# uStar_v1.net
KiCad netlist of a schematic drawn in EAGLE
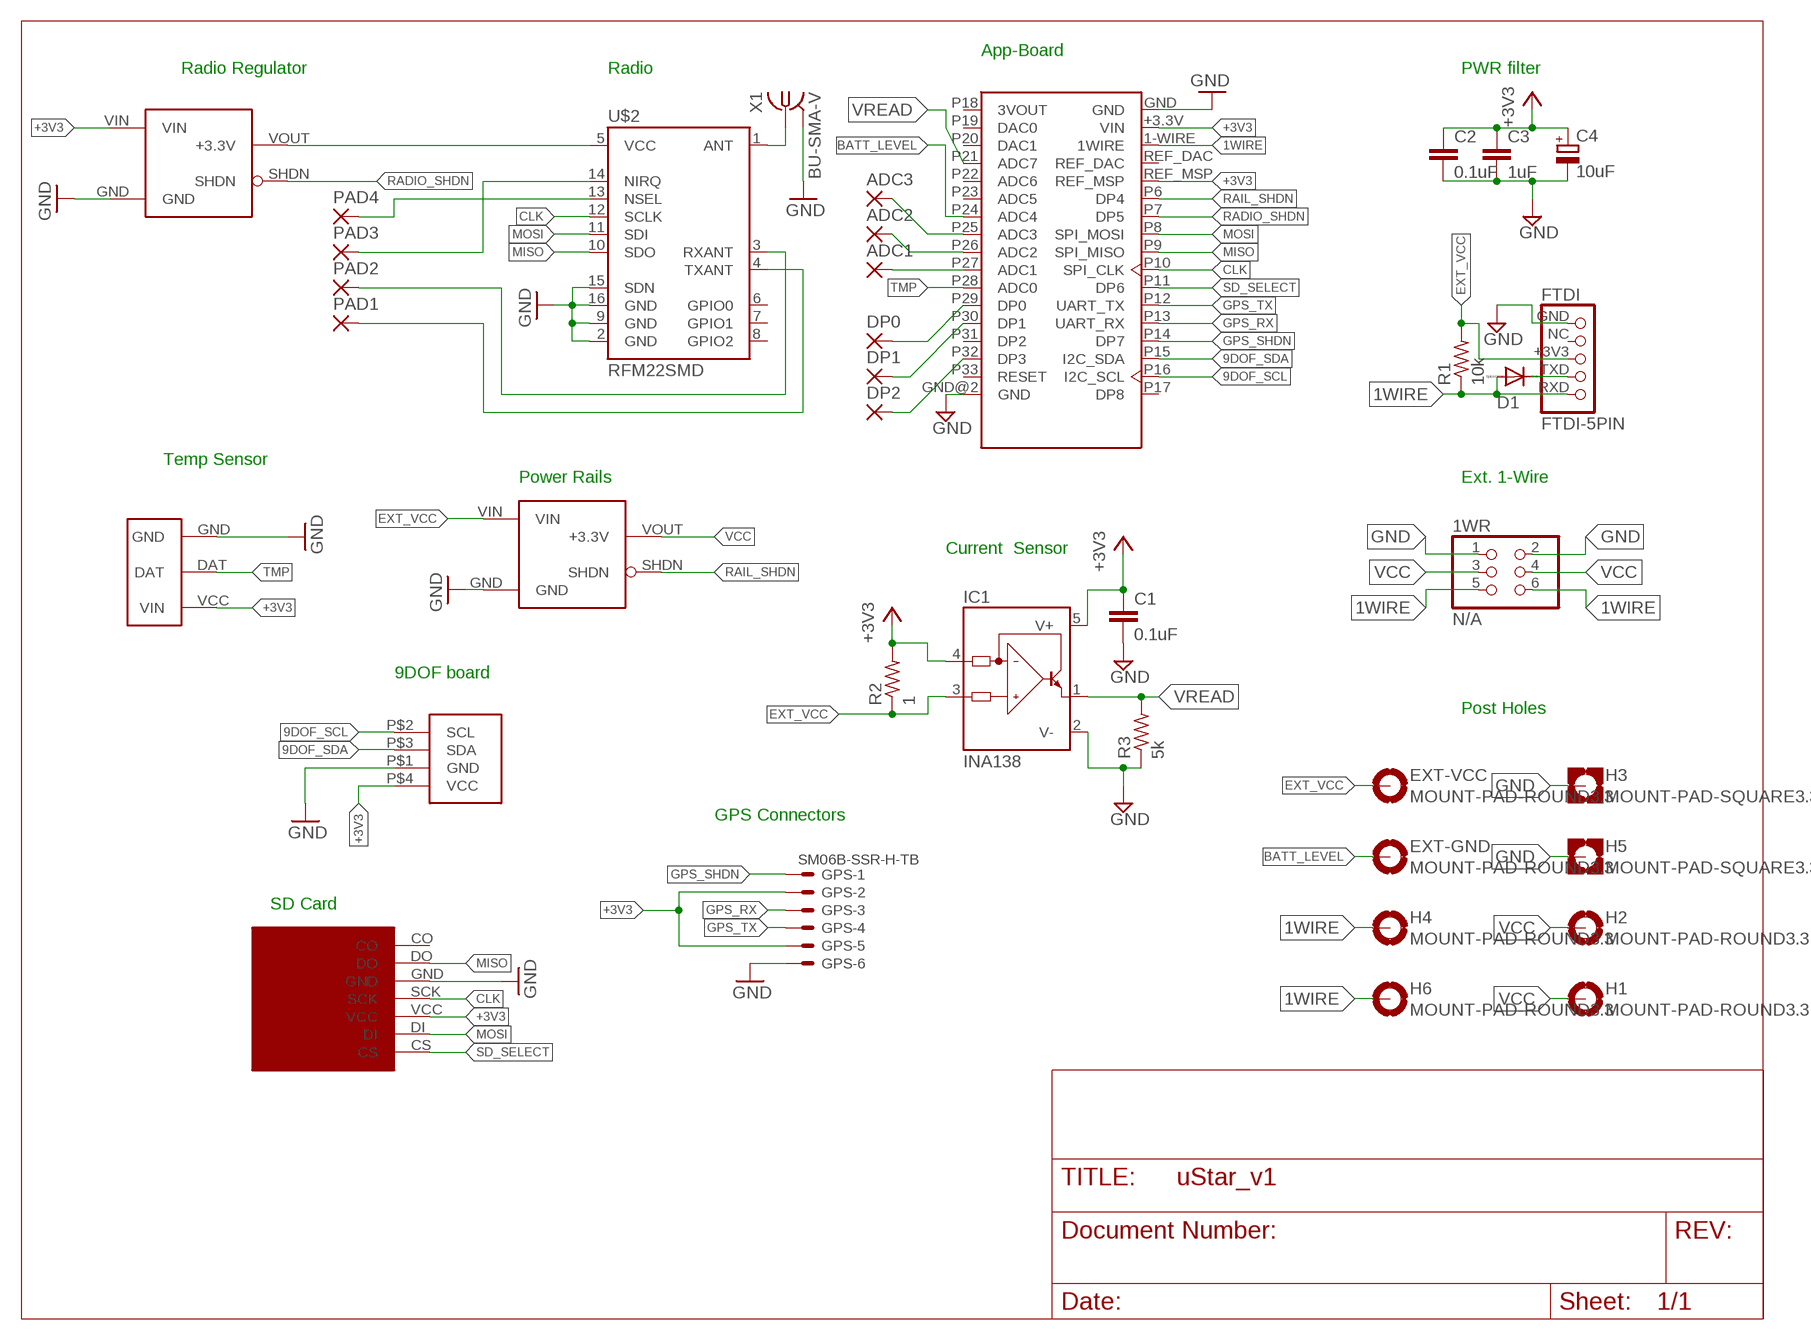
[diagram p0: schematic, sheet 1]

(export (version "E")
  (design (tool "Eeschema 10.0.6"))
  (components
    (comp (ref "1WR")
      (value "N/A")
      (footprint "eagle-import:2X03")
      (libsource (lib "eagle-import") (part "PINHD-2X3"))
    )
    (comp (ref "ADC1")
      (value "1,6/0,9")
      (footprint "eagle-import:1,6_0,9")
      (libsource (lib "eagle-import") (part "1,6/0,9"))
    )
    (comp (ref "ADC2")
      (value "1,6/0,9")
      (footprint "eagle-import:1,6_0,9")
      (libsource (lib "eagle-import") (part "1,6/0,9"))
    )
    (comp (ref "ADC3")
      (value "1,6/0,9")
      (footprint "eagle-import:1,6_0,9")
      (libsource (lib "eagle-import") (part "1,6/0,9"))
    )
    (comp (ref "C1")
      (value "0.1uF")
      (footprint "eagle-import:C0805")
      (libsource (lib "eagle-import") (part "C-EUC0805"))
    )
    (comp (ref "C2")
      (value "0.1uF")
      (footprint "eagle-import:C0603")
      (libsource (lib "eagle-import") (part "C-EUC0603"))
    )
    (comp (ref "C3")
      (value "1uF")
      (footprint "eagle-import:C0603")
      (libsource (lib "eagle-import") (part "C-EUC0603"))
    )
    (comp (ref "C4")
      (value "10uF")
      (footprint "eagle-import:SMC_B")
      (libsource (lib "eagle-import") (part "CPOL-EUSMCB"))
    )
    (comp (ref "D1")
      (value "1N4148DO35-7")
      (footprint "eagle-import:DO35-7")
      (libsource (lib "eagle-import") (part "1N4148DO35-7"))
    )
    (comp (ref "DP0")
      (value "1,6/0,9")
      (footprint "eagle-import:1,6_0,9")
      (libsource (lib "eagle-import") (part "1,6/0,9"))
    )
    (comp (ref "DP1")
      (value "1,6/0,9")
      (footprint "eagle-import:1,6_0,9")
      (libsource (lib "eagle-import") (part "1,6/0,9"))
    )
    (comp (ref "DP2")
      (value "1,6/0,9")
      (footprint "eagle-import:1,6_0,9")
      (libsource (lib "eagle-import") (part "1,6/0,9"))
    )
    (comp (ref "EXT-GND")
      (value "MOUNT-PAD-ROUND3.3")
      (footprint "eagle-import:3,3-PAD")
      (libsource (lib "eagle-import") (part "MOUNT-PAD-ROUND3.3"))
    )
    (comp (ref "EXT-VCC")
      (value "MOUNT-PAD-ROUND3.3")
      (footprint "eagle-import:3,3-PAD")
      (libsource (lib "eagle-import") (part "MOUNT-PAD-ROUND3.3"))
    )
    (comp (ref "FTDI")
      (value "FTDI-5PIN")
      (footprint "eagle-import:1_05X2MM")
      (libsource (lib "eagle-import") (part "FTDI-5PIN"))
    )
    (comp (ref "GPS")
      (value "SM06B-SSR-H-TB")
      (footprint "eagle-import:SM06B-SSR-H-TB")
      (libsource (lib "eagle-import") (part "SM06B-SSR-H-TB"))
    )
    (comp (ref "H1")
      (value "MOUNT-PAD-ROUND3.3")
      (footprint "eagle-import:3,3-PAD")
      (libsource (lib "eagle-import") (part "MOUNT-PAD-ROUND3.3"))
    )
    (comp (ref "H2")
      (value "MOUNT-PAD-ROUND3.3")
      (footprint "eagle-import:3,3-PAD")
      (libsource (lib "eagle-import") (part "MOUNT-PAD-ROUND3.3"))
    )
    (comp (ref "H3")
      (value "MOUNT-PAD-SQUARE3.3")
      (footprint "eagle-import:3,3-PAD-SQUARE")
      (libsource (lib "eagle-import") (part "MOUNT-PAD-SQUARE3.3"))
    )
    (comp (ref "H4")
      (value "MOUNT-PAD-ROUND3.3")
      (footprint "eagle-import:3,3-PAD")
      (libsource (lib "eagle-import") (part "MOUNT-PAD-ROUND3.3"))
    )
    (comp (ref "H5")
      (value "MOUNT-PAD-SQUARE3.3")
      (footprint "eagle-import:3,3-PAD-SQUARE")
      (libsource (lib "eagle-import") (part "MOUNT-PAD-SQUARE3.3"))
    )
    (comp (ref "H6")
      (value "MOUNT-PAD-ROUND3.3")
      (footprint "eagle-import:3,3-PAD")
      (libsource (lib "eagle-import") (part "MOUNT-PAD-ROUND3.3"))
    )
    (comp (ref "IC1")
      (value "INA138")
      (footprint "eagle-import:SOT23-5")
      (fields (field (name "MF") "TEXAS INSTRUMENTS") (field (name "MPN") "INA138NA/250"))
      (libsource (lib "eagle-import") (part "INA138"))
    )
    (comp (ref "PAD1")
      (value "1,6/0,9")
      (footprint "eagle-import:1,6_0,9")
      (libsource (lib "eagle-import") (part "1,6/0,9"))
    )
    (comp (ref "PAD2")
      (value "1,6/0,9")
      (footprint "eagle-import:1,6_0,9")
      (libsource (lib "eagle-import") (part "1,6/0,9"))
    )
    (comp (ref "PAD3")
      (value "1,6/0,9")
      (footprint "eagle-import:1,6_0,9")
      (libsource (lib "eagle-import") (part "1,6/0,9"))
    )
    (comp (ref "PAD4")
      (value "1,6/0,9")
      (footprint "eagle-import:1,6_0,9")
      (libsource (lib "eagle-import") (part "1,6/0,9"))
    )
    (comp (ref "R1")
      (value "10k")
      (footprint "eagle-import:0207_7")
      (libsource (lib "eagle-import") (part "R-US_0207/7"))
    )
    (comp (ref "R2")
      (value "1")
      (footprint "eagle-import:R0603")
      (libsource (lib "eagle-import") (part "R-US_R0603"))
    )
    (comp (ref "R3")
      (value "5k")
      (footprint "eagle-import:R0603")
      (libsource (lib "eagle-import") (part "R-US_R0603"))
    )
    (comp (ref "U$1")
      (value "App-Board 1.2/1.3")
      (footprint "eagle-import:APPCORE_RECEIVER")
      (libsource (lib "eagle-import") (part "APP_CORE"))
    )
    (comp (ref "U$2")
      (value "RFM22SMD")
      (footprint "eagle-import:RFM22-XXX-S2")
      (libsource (lib "eagle-import") (part "RFM22SMD"))
    )
    (comp (ref "U$3")
      (value "S7V8F3_VOLT_REG-3V3_1AHORZ-DOWN")
      (footprint "eagle-import:S7V_DOWN")
      (libsource (lib "eagle-import") (part "S7V8F3_VOLT_REG-3V3_1AHORZ-DOWN"))
    )
    (comp (ref "U$4")
      (value "TMP_EXT")
      (footprint "eagle-import:TMP_EXT")
      (libsource (lib "eagle-import") (part "TMP_EXT"))
    )
    (comp (ref "U$5")
      (value "9DOF")
      (footprint "eagle-import:9DOF")
      (libsource (lib "eagle-import") (part "9DOF"))
    )
    (comp (ref "U$6")
      (value "BOB-00544")
      (footprint "eagle-import:BOB-00544")
      (libsource (lib "eagle-import") (part "BOB-00544"))
    )
    (comp (ref "U$7")
      (value "S7V8F3_VOLT_REG-3V3_1AHORZ-DOWN")
      (footprint "eagle-import:S7V_DOWN")
      (libsource (lib "eagle-import") (part "S7V8F3_VOLT_REG-3V3_1AHORZ-DOWN"))
    )
    (comp (ref "X1")
      (value "BU-SMA-V")
      (footprint "eagle-import:BU-SMA-V")
      (libsource (lib "eagle-import") (part "BU-SMA-V"))
    )
  )
  (nets
    (net (code "1") (name "+3V3") (class "Default")
      (node (ref "C1") (pin "1") (pinfunction "1_1") (pintype "passive"))
      (node (ref "C2") (pin "1") (pinfunction "1_1") (pintype "passive"))
      (node (ref "C3") (pin "1") (pinfunction "1_1") (pintype "passive"))
      (node (ref "C4") (pin "+") (pinfunction "+_+") (pintype "passive"))
      (node (ref "GPS") (pin "2") (pinfunction "S_2") (pintype "passive"))
      (node (ref "GPS") (pin "5") (pinfunction "S_5") (pintype "passive"))
      (node (ref "IC1") (pin "4") (pinfunction "IN-_4") (pintype "input"))
      (node (ref "IC1") (pin "5") (pinfunction "V+_5") (pintype "power_in"))
      (node (ref "R2") (pin "2") (pinfunction "2_2") (pintype "passive"))
      (node (ref "U$1") (pin "+3.3V") (pinfunction "VIN_+3.3V") (pintype "power_in"))
      (node (ref "U$1") (pin "REF_MSP") (pinfunction "REF_MSP_REF_MSP") (pintype "input"))
      (node (ref "U$3") (pin "VIN") (pinfunction "VIN_VIN") (pintype "power_in"))
      (node (ref "U$4") (pin "VCC") (pinfunction "VIN_VCC") (pintype "bidirectional"))
      (node (ref "U$5") (pin "P$4") (pinfunction "VCC_P$4") (pintype "bidirectional"))
      (node (ref "U$6") (pin "VCC") (pinfunction "VCC_VCC") (pintype "bidirectional"))
    )
    (net (code "2") (name "1WIRE") (class "Default")
      (node (ref "1WR") (pin "5") (pinfunction "5_5") (pintype "passive"))
      (node (ref "1WR") (pin "6") (pinfunction "6_6") (pintype "passive"))
      (node (ref "D1") (pin "A") (pinfunction "A_A") (pintype "passive"))
      (node (ref "FTDI") (pin "RXD") (pinfunction "RXD_RXD") (pintype "input"))
      (node (ref "H4") (pin "B3,3") (pinfunction "MOUNT_B3,3") (pintype "passive"))
      (node (ref "H6") (pin "B3,3") (pinfunction "MOUNT_B3,3") (pintype "passive"))
      (node (ref "R1") (pin "1") (pinfunction "1_1") (pintype "passive"))
      (node (ref "U$1") (pin "1-WIRE") (pinfunction "1WIRE_1-WIRE") (pintype "bidirectional"))
    )
    (net (code "3") (name "9DOF_SCL") (class "Default")
      (node (ref "U$1") (pin "P16") (pinfunction "I2C_SCL_P16") (pintype "bidirectional"))
      (node (ref "U$5") (pin "P$2") (pinfunction "SCL_P$2") (pintype "bidirectional"))
    )
    (net (code "4") (name "9DOF_SDA") (class "Default")
      (node (ref "U$1") (pin "P15") (pinfunction "I2C_SDA_P15") (pintype "bidirectional"))
      (node (ref "U$5") (pin "P$3") (pinfunction "SDA_P$3") (pintype "bidirectional"))
    )
    (net (code "5") (name "BATT_LEVEL") (class "Default")
      (node (ref "EXT-GND") (pin "B3,3") (pinfunction "MOUNT_B3,3") (pintype "passive"))
      (node (ref "U$1") (pin "P24") (pinfunction "ADC4_P24") (pintype "input"))
    )
    (net (code "6") (name "CLK") (class "Default")
      (node (ref "U$1") (pin "P10") (pinfunction "SPI_CLK_P10") (pintype "bidirectional"))
      (node (ref "U$2") (pin "12") (pinfunction "SCLK_12") (pintype "input"))
      (node (ref "U$6") (pin "SCK") (pinfunction "SCK_SCK") (pintype "bidirectional"))
    )
    (net (code "7") (name "EXT_VCC") (class "Default")
      (node (ref "EXT-VCC") (pin "B3,3") (pinfunction "MOUNT_B3,3") (pintype "passive"))
      (node (ref "FTDI") (pin "+3V3") (pinfunction "+3V3_+3V3") (pintype "power_in"))
      (node (ref "IC1") (pin "3") (pinfunction "IN+_3") (pintype "input"))
      (node (ref "R1") (pin "2") (pinfunction "2_2") (pintype "passive"))
      (node (ref "R2") (pin "1") (pinfunction "1_1") (pintype "passive"))
      (node (ref "U$7") (pin "VIN") (pinfunction "VIN_VIN") (pintype "power_in"))
    )
    (net (code "8") (name "GND") (class "Default")
      (node (ref "1WR") (pin "1") (pinfunction "1_1") (pintype "passive"))
      (node (ref "1WR") (pin "2") (pinfunction "2_2") (pintype "passive"))
      (node (ref "C1") (pin "2") (pinfunction "2_2") (pintype "passive"))
      (node (ref "C2") (pin "2") (pinfunction "2_2") (pintype "passive"))
      (node (ref "C3") (pin "2") (pinfunction "2_2") (pintype "passive"))
      (node (ref "C4") (pin "-") (pinfunction "-_-") (pintype "passive"))
      (node (ref "FTDI") (pin "GND") (pinfunction "GND_GND") (pintype "power_in"))
      (node (ref "GPS") (pin "6") (pinfunction "S_6") (pintype "passive"))
      (node (ref "H3") (pin "B3,3") (pinfunction "MOUNT_B3,3") (pintype "passive"))
      (node (ref "H5") (pin "B3,3") (pinfunction "MOUNT_B3,3") (pintype "passive"))
      (node (ref "IC1") (pin "2") (pinfunction "V-_2") (pintype "power_in"))
      (node (ref "R3") (pin "1") (pinfunction "1_1") (pintype "passive"))
      (node (ref "U$1") (pin "GND") (pinfunction "GND_GND") (pintype "power_in"))
      (node (ref "U$1") (pin "GND@2") (pinfunction "GND_GND@2") (pintype "power_in"))
      (node (ref "U$2") (pin "15") (pinfunction "SDN_15") (pintype "input"))
      (node (ref "U$2") (pin "16") (pinfunction "GND_16") (pintype "power_in"))
      (node (ref "U$2") (pin "2") (pinfunction "GND_2") (pintype "power_in"))
      (node (ref "U$2") (pin "9") (pinfunction "GND_9") (pintype "power_in"))
      (node (ref "U$3") (pin "GND") (pinfunction "GND_GND") (pintype "power_in"))
      (node (ref "U$4") (pin "GND") (pinfunction "GND_GND") (pintype "bidirectional"))
      (node (ref "U$5") (pin "P$1") (pinfunction "GND_P$1") (pintype "bidirectional"))
      (node (ref "U$6") (pin "GND") (pinfunction "GND_GND") (pintype "bidirectional"))
      (node (ref "U$7") (pin "GND") (pinfunction "GND_GND") (pintype "power_in"))
      (node (ref "X1") (pin "2") (pinfunction "2_2") (pintype "passive"))
      (node (ref "X1") (pin "3") (pinfunction "2_3") (pintype "passive"))
      (node (ref "X1") (pin "4") (pinfunction "2_4") (pintype "passive"))
      (node (ref "X1") (pin "5") (pinfunction "2_5") (pintype "passive"))
    )
    (net (code "9") (name "GPS_RX") (class "Default")
      (node (ref "GPS") (pin "3") (pinfunction "S_3") (pintype "passive"))
      (node (ref "U$1") (pin "P13") (pinfunction "UART_RX_P13") (pintype "input"))
    )
    (net (code "10") (name "GPS_SHDN") (class "Default")
      (node (ref "GPS") (pin "1") (pinfunction "S_1") (pintype "passive"))
      (node (ref "U$1") (pin "P14") (pinfunction "DP7_P14") (pintype "bidirectional"))
    )
    (net (code "11") (name "GPS_TX") (class "Default")
      (node (ref "GPS") (pin "4") (pinfunction "S_4") (pintype "passive"))
      (node (ref "U$1") (pin "P12") (pinfunction "UART_TX_P12") (pintype "output"))
    )
    (net (code "12") (name "MISO") (class "Default")
      (node (ref "U$1") (pin "P9") (pinfunction "SPI_MISO_P9") (pintype "bidirectional"))
      (node (ref "U$2") (pin "10") (pinfunction "SDO_10") (pintype "output"))
      (node (ref "U$6") (pin "DO") (pinfunction "DO_DO") (pintype "bidirectional"))
    )
    (net (code "13") (name "MOSI") (class "Default")
      (node (ref "U$1") (pin "P8") (pinfunction "SPI_MOSI_P8") (pintype "bidirectional"))
      (node (ref "U$2") (pin "11") (pinfunction "SDI_11") (pintype "input"))
      (node (ref "U$6") (pin "DI") (pinfunction "DI_DI") (pintype "bidirectional"))
    )
    (net (code "14") (name "Net-(ADC1-P)") (class "Default")
      (node (ref "ADC1") (pin "1") (pinfunction "P_1") (pintype "passive"))
      (node (ref "U$1") (pin "P27") (pinfunction "ADC1_P27") (pintype "input"))
    )
    (net (code "15") (name "Net-(ADC2-P)") (class "Default")
      (node (ref "ADC2") (pin "1") (pinfunction "P_1") (pintype "passive"))
      (node (ref "U$1") (pin "P26") (pinfunction "ADC2_P26") (pintype "input"))
    )
    (net (code "16") (name "Net-(ADC3-P)") (class "Default")
      (node (ref "ADC3") (pin "1") (pinfunction "P_1") (pintype "passive"))
      (node (ref "U$1") (pin "P25") (pinfunction "ADC3_P25") (pintype "input"))
    )
    (net (code "17") (name "Net-(D1-PadC)") (class "Default")
      (node (ref "D1") (pin "C") (pinfunction "C_C") (pintype "passive"))
      (node (ref "FTDI") (pin "TXD") (pinfunction "TXD_TXD") (pintype "output"))
    )
    (net (code "18") (name "Net-(DP0-P)") (class "Default")
      (node (ref "DP0") (pin "1") (pinfunction "P_1") (pintype "passive"))
      (node (ref "U$1") (pin "P29") (pinfunction "DP0_P29") (pintype "bidirectional"))
    )
    (net (code "19") (name "Net-(DP1-P)") (class "Default")
      (node (ref "DP1") (pin "1") (pinfunction "P_1") (pintype "passive"))
      (node (ref "U$1") (pin "P30") (pinfunction "DP1_P30") (pintype "bidirectional"))
    )
    (net (code "20") (name "Net-(DP2-P)") (class "Default")
      (node (ref "DP2") (pin "1") (pinfunction "P_1") (pintype "passive"))
      (node (ref "U$1") (pin "P32") (pinfunction "DP3_P32") (pintype "bidirectional"))
    )
    (net (code "21") (name "Net-(PAD1-P)") (class "Default")
      (node (ref "PAD1") (pin "1") (pinfunction "P_1") (pintype "passive"))
      (node (ref "U$2") (pin "4") (pinfunction "TXANT_4") (pintype "input"))
    )
    (net (code "22") (name "Net-(PAD2-P)") (class "Default")
      (node (ref "PAD2") (pin "1") (pinfunction "P_1") (pintype "passive"))
      (node (ref "U$2") (pin "3") (pinfunction "RXANT_3") (pintype "input"))
    )
    (net (code "23") (name "Net-(PAD3-P)") (class "Default")
      (node (ref "PAD3") (pin "1") (pinfunction "P_1") (pintype "passive"))
      (node (ref "U$2") (pin "14") (pinfunction "NIRQ_14") (pintype "output"))
    )
    (net (code "24") (name "Net-(PAD4-P)") (class "Default")
      (node (ref "PAD4") (pin "1") (pinfunction "P_1") (pintype "passive"))
      (node (ref "U$2") (pin "13") (pinfunction "NSEL_13") (pintype "input"))
    )
    (net (code "25") (name "Net-(U$2-ANT)") (class "Default")
      (node (ref "U$2") (pin "1") (pinfunction "ANT_1") (pintype "bidirectional"))
      (node (ref "X1") (pin "1") (pinfunction "1_1") (pintype "passive"))
    )
    (net (code "26") (name "Net-(U$2-VCC)") (class "Default")
      (node (ref "U$2") (pin "5") (pinfunction "VCC_5") (pintype "bidirectional"))
      (node (ref "U$3") (pin "VOUT") (pinfunction "+3.3V_VOUT") (pintype "output"))
    )
    (net (code "27") (name "RADIO_SHDN") (class "Default")
      (node (ref "U$1") (pin "P7") (pinfunction "DP5_P7") (pintype "bidirectional"))
      (node (ref "U$3") (pin "SHDN") (pinfunction "SHDN_SHDN") (pintype "input"))
    )
    (net (code "28") (name "RAIL_SHDN") (class "Default")
      (node (ref "U$1") (pin "P6") (pinfunction "DP4_P6") (pintype "bidirectional"))
      (node (ref "U$7") (pin "SHDN") (pinfunction "SHDN_SHDN") (pintype "input"))
    )
    (net (code "29") (name "SD_SELECT") (class "Default")
      (node (ref "U$1") (pin "P11") (pinfunction "DP6_P11") (pintype "bidirectional"))
      (node (ref "U$6") (pin "CS") (pinfunction "CS_CS") (pintype "bidirectional"))
    )
    (net (code "30") (name "TMP") (class "Default")
      (node (ref "U$1") (pin "P28") (pinfunction "ADC0_P28") (pintype "input"))
      (node (ref "U$4") (pin "DAT") (pinfunction "DAT_DAT") (pintype "bidirectional"))
    )
    (net (code "31") (name "VCC") (class "Default")
      (node (ref "1WR") (pin "3") (pinfunction "3_3") (pintype "passive"))
      (node (ref "1WR") (pin "4") (pinfunction "4_4") (pintype "passive"))
      (node (ref "H1") (pin "B3,3") (pinfunction "MOUNT_B3,3") (pintype "passive"))
      (node (ref "H2") (pin "B3,3") (pinfunction "MOUNT_B3,3") (pintype "passive"))
      (node (ref "U$7") (pin "VOUT") (pinfunction "+3.3V_VOUT") (pintype "output"))
    )
    (net (code "32") (name "VREAD") (class "Default")
      (node (ref "IC1") (pin "1") (pinfunction "OUT_1") (pintype "output"))
      (node (ref "R3") (pin "2") (pinfunction "2_2") (pintype "passive"))
      (node (ref "U$1") (pin "P21") (pinfunction "ADC7_P21") (pintype "input"))
    )
    (net (code "33") (name "unconnected-(FTDI-PadNC)") (class "Default")
      (node (ref "FTDI") (pin "NC") (pinfunction "NC_NC") (pintype "no_connect"))
    )
    (net (code "34") (name "unconnected-(U$1-3VOUT-PadP18)") (class "Default")
      (node (ref "U$1") (pin "P18") (pinfunction "3VOUT_P18") (pintype "output"))
    )
    (net (code "35") (name "unconnected-(U$1-ADC5-PadP23)") (class "Default")
      (node (ref "U$1") (pin "P23") (pinfunction "ADC5_P23") (pintype "input"))
    )
    (net (code "36") (name "unconnected-(U$1-ADC6-PadP22)") (class "Default")
      (node (ref "U$1") (pin "P22") (pinfunction "ADC6_P22") (pintype "input"))
    )
    (net (code "37") (name "unconnected-(U$1-DAC0-PadP19)") (class "Default")
      (node (ref "U$1") (pin "P19") (pinfunction "DAC0_P19") (pintype "bidirectional"))
    )
    (net (code "38") (name "unconnected-(U$1-DAC1-PadP20)") (class "Default")
      (node (ref "U$1") (pin "P20") (pinfunction "DAC1_P20") (pintype "bidirectional"))
    )
    (net (code "39") (name "unconnected-(U$1-DP2-PadP31)") (class "Default")
      (node (ref "U$1") (pin "P31") (pinfunction "DP2_P31") (pintype "bidirectional"))
    )
    (net (code "40") (name "unconnected-(U$1-DP8-PadP17)") (class "Default")
      (node (ref "U$1") (pin "P17") (pinfunction "DP8_P17") (pintype "bidirectional"))
    )
    (net (code "41") (name "unconnected-(U$1-PadREF_DAC)") (class "Default")
      (node (ref "U$1") (pin "REF_DAC") (pinfunction "REF_DAC_REF_DAC") (pintype "input"))
    )
    (net (code "42") (name "unconnected-(U$1-RESET-PadP33)") (class "Default")
      (node (ref "U$1") (pin "P33") (pinfunction "RESET_P33") (pintype "bidirectional"))
    )
    (net (code "43") (name "unconnected-(U$2-GPIO0-Pad6)") (class "Default")
      (node (ref "U$2") (pin "6") (pinfunction "GPIO0_6") (pintype "bidirectional"))
    )
    (net (code "44") (name "unconnected-(U$2-GPIO1-Pad7)") (class "Default")
      (node (ref "U$2") (pin "7") (pinfunction "GPIO1_7") (pintype "bidirectional"))
    )
    (net (code "45") (name "unconnected-(U$2-GPIO2-Pad8)") (class "Default")
      (node (ref "U$2") (pin "8") (pinfunction "GPIO2_8") (pintype "bidirectional"))
    )
    (net (code "46") (name "unconnected-(U$6-PadCO)") (class "Default")
      (node (ref "U$6") (pin "CO") (pinfunction "CO_CO") (pintype "bidirectional"))
    )
  )
)
